# Fluxamasynth32.net
KiCad netlist of a schematic drawn in EAGLE
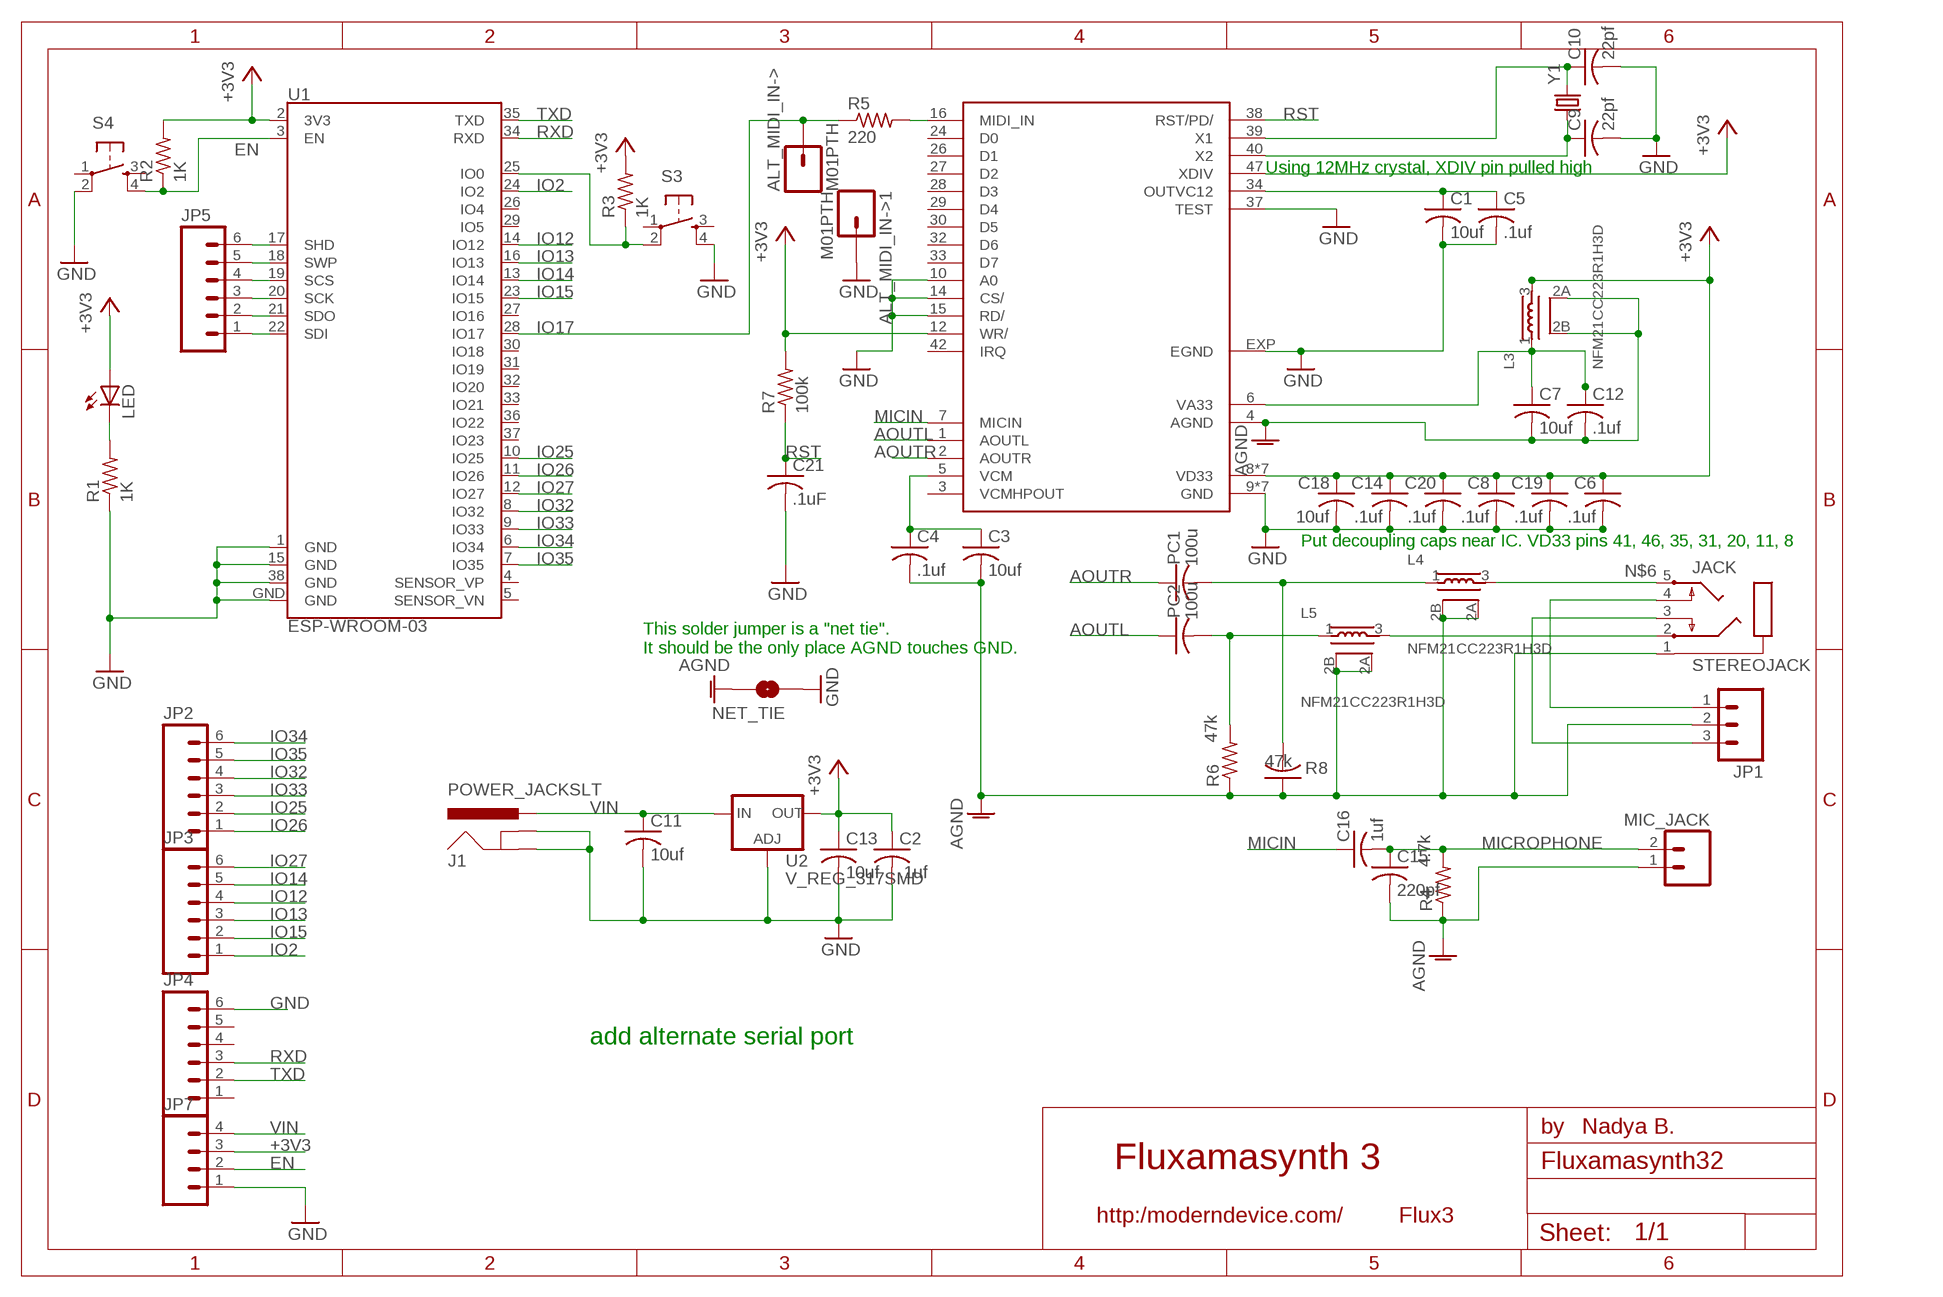
[diagram p0: schematic, sheet 1]

(export (version "E")
  (design (tool "Eeschema 10.0.6"))
  (components
    (comp (ref "ALT_MIDI_IN->")
      (value "M01PTH")
      (footprint "eagle-import:1X01")
      (libsource (lib "eagle-import") (part "M01PTH"))
    )
    (comp (ref "ALT_MIDI_IN->1")
      (value "M01PTH")
      (footprint "eagle-import:1X01")
      (libsource (lib "eagle-import") (part "M01PTH"))
    )
    (comp (ref "C1")
      (value "10uf")
      (footprint "eagle-import:C0805K")
      (libsource (lib "eagle-import") (part "C-USC0805K"))
    )
    (comp (ref "C2")
      (value ".1uf")
      (footprint "eagle-import:C0603K")
      (libsource (lib "eagle-import") (part "C-USC0603K"))
    )
    (comp (ref "C3")
      (value "10uf")
      (footprint "eagle-import:C0805K")
      (libsource (lib "eagle-import") (part "C-USC0805K"))
    )
    (comp (ref "C4")
      (value ".1uf")
      (footprint "eagle-import:C0603K")
      (libsource (lib "eagle-import") (part "C-USC0603K"))
    )
    (comp (ref "C5")
      (value ".1uf")
      (footprint "eagle-import:C0603K")
      (libsource (lib "eagle-import") (part "C-USC0603K"))
    )
    (comp (ref "C6")
      (value ".1uf")
      (footprint "eagle-import:C0603K")
      (libsource (lib "eagle-import") (part "C-USC0603K"))
    )
    (comp (ref "C7")
      (value "10uf")
      (footprint "eagle-import:C0805K")
      (libsource (lib "eagle-import") (part "C-USC0805K"))
    )
    (comp (ref "C8")
      (value ".1uf")
      (footprint "eagle-import:C0603K")
      (libsource (lib "eagle-import") (part "C-USC0603K"))
    )
    (comp (ref "C9")
      (value "22pf")
      (footprint "eagle-import:C0603")
      (libsource (lib "eagle-import") (part "C-USC0603"))
    )
    (comp (ref "C10")
      (value "22pf")
      (footprint "eagle-import:C0603")
      (libsource (lib "eagle-import") (part "C-USC0603"))
    )
    (comp (ref "C11")
      (value "10uf")
      (footprint "eagle-import:C1206")
      (libsource (lib "eagle-import") (part "C-USC1206"))
    )
    (comp (ref "C12")
      (value ".1uf")
      (footprint "eagle-import:C0603K")
      (libsource (lib "eagle-import") (part "C-USC0603K"))
    )
    (comp (ref "C13")
      (value "10uf")
      (footprint "eagle-import:C1206")
      (libsource (lib "eagle-import") (part "C-USC1206"))
    )
    (comp (ref "C14")
      (value ".1uf")
      (footprint "eagle-import:C0603K")
      (libsource (lib "eagle-import") (part "C-USC0603K"))
    )
    (comp (ref "C15")
      (value "220pf")
      (footprint "eagle-import:C0805K")
      (libsource (lib "eagle-import") (part "C-USC0805K"))
    )
    (comp (ref "C16")
      (value "1uf")
      (footprint "eagle-import:C0603K")
      (libsource (lib "eagle-import") (part "C-USC0603K"))
    )
    (comp (ref "C18")
      (value "10uf")
      (footprint "eagle-import:C0603K")
      (libsource (lib "eagle-import") (part "C-USC0603K"))
    )
    (comp (ref "C19")
      (value ".1uf")
      (footprint "eagle-import:C0603K")
      (libsource (lib "eagle-import") (part "C-USC0603K"))
    )
    (comp (ref "C20")
      (value ".1uf")
      (footprint "eagle-import:C0603K")
      (libsource (lib "eagle-import") (part "C-USC0603K"))
    )
    (comp (ref "C21")
      (value ".1uF")
      (footprint "eagle-import:C0603K")
      (libsource (lib "eagle-import") (part "C-USC0603K"))
    )
    (comp (ref "J1")
      (value "POWER_JACKSLT")
      (footprint "eagle-import:POWER_JACK_SLOT")
      (libsource (lib "eagle-import") (part "POWER_JACKSLT"))
    )
    (comp (ref "JACK")
      (value "STEREOJACK")
      (footprint "eagle-import:STX3100")
      (libsource (lib "eagle-import") (part "STEREOJACK"))
    )
    (comp (ref "JP1")
      (value "M03PTH")
      (footprint "eagle-import:1X03")
      (libsource (lib "eagle-import") (part "M03PTH"))
    )
    (comp (ref "JP2")
      (value "M06NO_SILK")
      (footprint "eagle-import:1X06_NO_SILK")
      (libsource (lib "eagle-import") (part "M06NO_SILK"))
    )
    (comp (ref "JP3")
      (value "M06NO_SILK")
      (footprint "eagle-import:1X06_NO_SILK")
      (libsource (lib "eagle-import") (part "M06NO_SILK"))
    )
    (comp (ref "JP4")
      (value "M06NO_SILK")
      (footprint "eagle-import:1X06_NO_SILK")
      (libsource (lib "eagle-import") (part "M06NO_SILK"))
    )
    (comp (ref "JP5")
      (value "M06NO_SILK")
      (footprint "eagle-import:1X06_NO_SILK")
      (libsource (lib "eagle-import") (part "M06NO_SILK"))
    )
    (comp (ref "JP7")
      (value "M041X04_NO_SILK")
      (footprint "eagle-import:1X04_NO_SILK")
      (libsource (lib "eagle-import") (part "M041X04_NO_SILK"))
    )
    (comp (ref "L3")
      (value "NFM21CC223R1H3D")
      (footprint "eagle-import:3PC")
      (libsource (lib "eagle-import") (part "NFM21CC223R1H3D"))
    )
    (comp (ref "L4")
      (value "NFM21CC223R1H3D")
      (footprint "eagle-import:3PC")
      (libsource (lib "eagle-import") (part "NFM21CC223R1H3D"))
    )
    (comp (ref "L5")
      (value "NFM21CC223R1H3D")
      (footprint "eagle-import:3PC")
      (libsource (lib "eagle-import") (part "NFM21CC223R1H3D"))
    )
    (comp (ref "LED")
      (value "LED0603")
      (footprint "eagle-import:LED-0603")
      (libsource (lib "eagle-import") (part "LED0603"))
    )
    (comp (ref "MIC_JACK")
      (value "M02PTH")
      (footprint "eagle-import:1X02")
      (libsource (lib "eagle-import") (part "M02PTH"))
    )
    (comp (ref "NET_TIE")
      (value "MODERNDEVICE_SOLDERJUMPERTRACE")
      (footprint "eagle-import:MODERNDEVICE_SJ_2S-TRACE")
      (libsource (lib "eagle-import") (part "MODERNDEVICE_SOLDERJUMPERTRACE"))
    )
    (comp (ref "PC1")
      (value "100u")
      (footprint "eagle-import:C1206K")
      (libsource (lib "eagle-import") (part "C-USC1206K"))
    )
    (comp (ref "PC2")
      (value "100u")
      (footprint "eagle-import:C1206K")
      (libsource (lib "eagle-import") (part "C-USC1206K"))
    )
    (comp (ref "R1")
      (value "1K")
      (footprint "eagle-import:R0603")
      (libsource (lib "eagle-import") (part "R-US_R0603"))
    )
    (comp (ref "R2")
      (value "1K")
      (footprint "eagle-import:R0603")
      (libsource (lib "eagle-import") (part "R-US_R0603"))
    )
    (comp (ref "R3")
      (value "1K")
      (footprint "eagle-import:R0603")
      (libsource (lib "eagle-import") (part "R-US_R0603"))
    )
    (comp (ref "R4")
      (value "4.7k")
      (footprint "eagle-import:R0603")
      (libsource (lib "eagle-import") (part "R-US_R0603"))
    )
    (comp (ref "R5")
      (value "220")
      (footprint "eagle-import:R0603")
      (libsource (lib "eagle-import") (part "R-US_R0603"))
    )
    (comp (ref "R6")
      (value "47k")
      (footprint "eagle-import:R0603")
      (libsource (lib "eagle-import") (part "R-US_R0603"))
    )
    (comp (ref "R7")
      (value "100k")
      (footprint "eagle-import:R0603")
      (libsource (lib "eagle-import") (part "R-US_R0603"))
    )
    (comp (ref "R8")
      (value "47k")
      (footprint "eagle-import:C0603K")
      (libsource (lib "eagle-import") (part "C-USC0603K"))
    )
    (comp (ref "S3")
      (value "6MM_SWITCH6MM_SWITCH")
      (footprint "eagle-import:6MM_SWITCH")
      (libsource (lib "eagle-import") (part "6MM_SWITCH6MM_SWITCH"))
    )
    (comp (ref "S4")
      (value "6MM_SWITCH6MM_SWITCH")
      (footprint "eagle-import:6MM_SWITCH")
      (libsource (lib "eagle-import") (part "6MM_SWITCH6MM_SWITCH"))
    )
    (comp (ref "SAM2695")
      (value "SAM2695")
      (footprint "eagle-import:QFN48")
      (libsource (lib "eagle-import") (part "SAM2695"))
    )
    (comp (ref "U1")
      (value "ESP-WROOM-03")
      (footprint "eagle-import:ESP-WROOM-03")
      (libsource (lib "eagle-import") (part "ESP-WROOM-03"))
    )
    (comp (ref "U2")
      (value "V_REG_317SMD")
      (footprint "eagle-import:SOT223")
      (libsource (lib "eagle-import") (part "V_REG_317SMD"))
    )
    (comp (ref "Y1")
      (value "CRYSTALTXC-7A")
      (footprint "eagle-import:CRYSTAL-TXC-7A")
      (libsource (lib "eagle-import") (part "CRYSTALTXC-7A"))
    )
  )
  (nets
    (net (code "1") (name "+3V3") (class "Default")
      (node (ref "C13") (pin "1") (pinfunction "1_1") (pintype "passive"))
      (node (ref "C14") (pin "1") (pinfunction "1_1") (pintype "passive"))
      (node (ref "C18") (pin "1") (pinfunction "1_1") (pintype "passive"))
      (node (ref "C19") (pin "1") (pinfunction "1_1") (pintype "passive"))
      (node (ref "C2") (pin "1") (pinfunction "1_1") (pintype "passive"))
      (node (ref "C20") (pin "1") (pinfunction "1_1") (pintype "passive"))
      (node (ref "C6") (pin "1") (pinfunction "1_1") (pintype "passive"))
      (node (ref "C8") (pin "1") (pinfunction "1_1") (pintype "passive"))
      (node (ref "JP7") (pin "3") (pinfunction "3_3") (pintype "passive"))
      (node (ref "L3") (pin "3") (pinfunction "3_3") (pintype "bidirectional"))
      (node (ref "LED") (pin "A") (pinfunction "A_A") (pintype "passive"))
      (node (ref "R2") (pin "2") (pinfunction "2_2") (pintype "passive"))
      (node (ref "R3") (pin "2") (pinfunction "2_2") (pintype "passive"))
      (node (ref "R7") (pin "2") (pinfunction "2_2") (pintype "passive"))
      (node (ref "SAM2695") (pin "11") (pinfunction "VD33_11") (pintype "power_in"))
      (node (ref "SAM2695") (pin "12") (pinfunction "WR/_12") (pintype "input"))
      (node (ref "SAM2695") (pin "20") (pinfunction "VD33_20") (pintype "power_in"))
      (node (ref "SAM2695") (pin "31") (pinfunction "VD33_31") (pintype "power_in"))
      (node (ref "SAM2695") (pin "35") (pinfunction "VD33_35") (pintype "power_in"))
      (node (ref "SAM2695") (pin "41") (pinfunction "VD33_41") (pintype "power_in"))
      (node (ref "SAM2695") (pin "46") (pinfunction "VD33_46") (pintype "power_in"))
      (node (ref "SAM2695") (pin "47") (pinfunction "XDIV_47") (pintype "input"))
      (node (ref "SAM2695") (pin "8") (pinfunction "VD33_8") (pintype "power_in"))
      (node (ref "U1") (pin "2") (pinfunction "3V3_2") (pintype "bidirectional"))
      (node (ref "U2") (pin "2") (pinfunction "OUT_2") (pintype "output"))
      (node (ref "U2") (pin "4") (pinfunction "OUT_4") (pintype "output"))
    )
    (net (code "2") (name "/AOUTL") (class "Default")
      (node (ref "PC2") (pin "1") (pinfunction "1_1") (pintype "passive"))
      (node (ref "SAM2695") (pin "1") (pinfunction "AOUTL_1") (pintype "output"))
    )
    (net (code "3") (name "/AOUTR") (class "Default")
      (node (ref "PC1") (pin "1") (pinfunction "1_1") (pintype "passive"))
      (node (ref "SAM2695") (pin "2") (pinfunction "AOUTR_2") (pintype "output"))
    )
    (net (code "4") (name "/EN") (class "Default")
      (node (ref "JP7") (pin "2") (pinfunction "2_2") (pintype "passive"))
      (node (ref "R2") (pin "1") (pinfunction "1_1") (pintype "passive"))
      (node (ref "S4") (pin "4") (pinfunction "S1_4") (pintype "passive"))
      (node (ref "U1") (pin "3") (pinfunction "EN_3") (pintype "bidirectional"))
    )
    (net (code "5") (name "/IO2") (class "Default")
      (node (ref "JP3") (pin "1") (pinfunction "1_1") (pintype "passive"))
      (node (ref "U1") (pin "24") (pinfunction "IO2_24") (pintype "bidirectional"))
    )
    (net (code "6") (name "/IO12") (class "Default")
      (node (ref "JP3") (pin "4") (pinfunction "4_4") (pintype "passive"))
      (node (ref "U1") (pin "14") (pinfunction "IO12_14") (pintype "bidirectional"))
    )
    (net (code "7") (name "/IO13") (class "Default")
      (node (ref "JP3") (pin "3") (pinfunction "3_3") (pintype "passive"))
      (node (ref "U1") (pin "16") (pinfunction "IO13_16") (pintype "bidirectional"))
    )
    (net (code "8") (name "/IO14") (class "Default")
      (node (ref "JP3") (pin "5") (pinfunction "5_5") (pintype "passive"))
      (node (ref "U1") (pin "13") (pinfunction "IO14_13") (pintype "bidirectional"))
    )
    (net (code "9") (name "/IO15") (class "Default")
      (node (ref "JP3") (pin "2") (pinfunction "2_2") (pintype "passive"))
      (node (ref "U1") (pin "23") (pinfunction "IO15_23") (pintype "bidirectional"))
    )
    (net (code "10") (name "/IO17") (class "Default")
      (node (ref "ALT_MIDI_IN->") (pin "1") (pinfunction "1_1") (pintype "passive"))
      (node (ref "R5") (pin "1") (pinfunction "1_1") (pintype "passive"))
      (node (ref "U1") (pin "28") (pinfunction "IO17_28") (pintype "bidirectional"))
    )
    (net (code "11") (name "/IO25") (class "Default")
      (node (ref "JP2") (pin "2") (pinfunction "2_2") (pintype "passive"))
      (node (ref "U1") (pin "10") (pinfunction "IO25_10") (pintype "bidirectional"))
    )
    (net (code "12") (name "/IO26") (class "Default")
      (node (ref "JP2") (pin "1") (pinfunction "1_1") (pintype "passive"))
      (node (ref "U1") (pin "11") (pinfunction "IO26_11") (pintype "bidirectional"))
    )
    (net (code "13") (name "/IO27") (class "Default")
      (node (ref "JP3") (pin "6") (pinfunction "6_6") (pintype "passive"))
      (node (ref "U1") (pin "12") (pinfunction "IO27_12") (pintype "bidirectional"))
    )
    (net (code "14") (name "/IO32") (class "Default")
      (node (ref "JP2") (pin "4") (pinfunction "4_4") (pintype "passive"))
      (node (ref "U1") (pin "8") (pinfunction "IO32_8") (pintype "bidirectional"))
    )
    (net (code "15") (name "/IO33") (class "Default")
      (node (ref "JP2") (pin "3") (pinfunction "3_3") (pintype "passive"))
      (node (ref "U1") (pin "9") (pinfunction "IO33_9") (pintype "bidirectional"))
    )
    (net (code "16") (name "/IO34") (class "Default")
      (node (ref "JP2") (pin "6") (pinfunction "6_6") (pintype "passive"))
      (node (ref "U1") (pin "6") (pinfunction "IO34_6") (pintype "bidirectional"))
    )
    (net (code "17") (name "/IO35") (class "Default")
      (node (ref "JP2") (pin "5") (pinfunction "5_5") (pintype "passive"))
      (node (ref "U1") (pin "7") (pinfunction "IO35_7") (pintype "bidirectional"))
    )
    (net (code "18") (name "/MICIN") (class "Default")
      (node (ref "C16") (pin "1") (pinfunction "1_1") (pintype "passive"))
      (node (ref "SAM2695") (pin "7") (pinfunction "MICIN_7") (pintype "input"))
    )
    (net (code "19") (name "/MICROPHONE") (class "Default")
      (node (ref "C15") (pin "1") (pinfunction "1_1") (pintype "passive"))
      (node (ref "C16") (pin "2") (pinfunction "2_2") (pintype "passive"))
      (node (ref "MIC_JACK") (pin "2") (pinfunction "2_2") (pintype "passive"))
      (node (ref "R4") (pin "2") (pinfunction "2_2") (pintype "passive"))
    )
    (net (code "20") (name "/N$6") (class "Default")
      (node (ref "JACK") (pin "5") (pinfunction "5_5") (pintype "passive"))
      (node (ref "L4") (pin "3") (pinfunction "3_3") (pintype "bidirectional"))
    )
    (net (code "21") (name "/RST") (class "Default")
      (node (ref "C21") (pin "1") (pinfunction "1_1") (pintype "passive"))
      (node (ref "R7") (pin "1") (pinfunction "1_1") (pintype "passive"))
      (node (ref "SAM2695") (pin "38") (pinfunction "RST/PD/_38") (pintype "input"))
    )
    (net (code "22") (name "/RXD") (class "Default")
      (node (ref "JP4") (pin "3") (pinfunction "3_3") (pintype "passive"))
      (node (ref "U1") (pin "34") (pinfunction "RXD_34") (pintype "bidirectional"))
    )
    (net (code "23") (name "/TXD") (class "Default")
      (node (ref "JP4") (pin "2") (pinfunction "2_2") (pintype "passive"))
      (node (ref "U1") (pin "35") (pinfunction "TXD_35") (pintype "bidirectional"))
    )
    (net (code "24") (name "/VIN") (class "Default")
      (node (ref "C11") (pin "1") (pinfunction "1_1") (pintype "passive"))
      (node (ref "J1") (pin "PWR") (pinfunction "PWR_PWR") (pintype "bidirectional"))
      (node (ref "JP7") (pin "4") (pinfunction "4_4") (pintype "passive"))
      (node (ref "U2") (pin "3") (pinfunction "IN_3") (pintype "input"))
    )
    (net (code "25") (name "AGND") (class "Default")
      (node (ref "C12") (pin "2") (pinfunction "2_2") (pintype "passive"))
      (node (ref "C15") (pin "2") (pinfunction "2_2") (pintype "passive"))
      (node (ref "C3") (pin "2") (pinfunction "2_2") (pintype "passive"))
      (node (ref "C4") (pin "2") (pinfunction "2_2") (pintype "passive"))
      (node (ref "C7") (pin "2") (pinfunction "2_2") (pintype "passive"))
      (node (ref "JACK") (pin "1") (pinfunction "1_1") (pintype "passive"))
      (node (ref "JP1") (pin "2") (pinfunction "2_2") (pintype "passive"))
      (node (ref "L3") (pin "2A") (pinfunction "2A_2A") (pintype "power_in"))
      (node (ref "L3") (pin "2B") (pinfunction "2B_2B") (pintype "power_in"))
      (node (ref "L4") (pin "2A") (pinfunction "2A_2A") (pintype "power_in"))
      (node (ref "L4") (pin "2B") (pinfunction "2B_2B") (pintype "power_in"))
      (node (ref "L5") (pin "2A") (pinfunction "2A_2A") (pintype "power_in"))
      (node (ref "L5") (pin "2B") (pinfunction "2B_2B") (pintype "power_in"))
      (node (ref "MIC_JACK") (pin "1") (pinfunction "1_1") (pintype "passive"))
      (node (ref "NET_TIE") (pin "2") (pinfunction "2_2") (pintype "passive"))
      (node (ref "R4") (pin "1") (pinfunction "1_1") (pintype "passive"))
      (node (ref "R6") (pin "1") (pinfunction "1_1") (pintype "passive"))
      (node (ref "R8") (pin "1") (pinfunction "1_1") (pintype "passive"))
      (node (ref "SAM2695") (pin "4") (pinfunction "AGND_4") (pintype "power_in"))
    )
    (net (code "26") (name "GND") (class "Default")
      (node (ref "ALT_MIDI_IN->1") (pin "1") (pinfunction "1_1") (pintype "passive"))
      (node (ref "C1") (pin "2") (pinfunction "2_2") (pintype "passive"))
      (node (ref "C10") (pin "2") (pinfunction "2_2") (pintype "passive"))
      (node (ref "C11") (pin "2") (pinfunction "2_2") (pintype "passive"))
      (node (ref "C13") (pin "2") (pinfunction "2_2") (pintype "passive"))
      (node (ref "C14") (pin "2") (pinfunction "2_2") (pintype "passive"))
      (node (ref "C18") (pin "2") (pinfunction "2_2") (pintype "passive"))
      (node (ref "C19") (pin "2") (pinfunction "2_2") (pintype "passive"))
      (node (ref "C2") (pin "2") (pinfunction "2_2") (pintype "passive"))
      (node (ref "C20") (pin "2") (pinfunction "2_2") (pintype "passive"))
      (node (ref "C21") (pin "2") (pinfunction "2_2") (pintype "passive"))
      (node (ref "C5") (pin "2") (pinfunction "2_2") (pintype "passive"))
      (node (ref "C6") (pin "2") (pinfunction "2_2") (pintype "passive"))
      (node (ref "C8") (pin "2") (pinfunction "2_2") (pintype "passive"))
      (node (ref "C9") (pin "2") (pinfunction "2_2") (pintype "passive"))
      (node (ref "J1") (pin "GND@1") (pinfunction "GNDBREAK_GND@1") (pintype "bidirectional"))
      (node (ref "J1") (pin "GND@2") (pinfunction "GND_GND@2") (pintype "bidirectional"))
      (node (ref "JP4") (pin "6") (pinfunction "6_6") (pintype "passive"))
      (node (ref "JP7") (pin "1") (pinfunction "1_1") (pintype "passive"))
      (node (ref "NET_TIE") (pin "1") (pinfunction "1_1") (pintype "passive"))
      (node (ref "R1") (pin "1") (pinfunction "1_1") (pintype "passive"))
      (node (ref "S3") (pin "4") (pinfunction "S1_4") (pintype "passive"))
      (node (ref "S4") (pin "2") (pinfunction "P1_2") (pintype "passive"))
      (node (ref "SAM2695") (pin "10") (pinfunction "A0_10") (pintype "input"))
      (node (ref "SAM2695") (pin "13") (pinfunction "GND_13") (pintype "power_in"))
      (node (ref "SAM2695") (pin "14") (pinfunction "CS/_14") (pintype "input"))
      (node (ref "SAM2695") (pin "15") (pinfunction "RD/_15") (pintype "input"))
      (node (ref "SAM2695") (pin "18") (pinfunction "GND_18") (pintype "power_in"))
      (node (ref "SAM2695") (pin "25") (pinfunction "GND_25") (pintype "power_in"))
      (node (ref "SAM2695") (pin "36") (pinfunction "GND_36") (pintype "power_in"))
      (node (ref "SAM2695") (pin "37") (pinfunction "TEST_37") (pintype "input"))
      (node (ref "SAM2695") (pin "45") (pinfunction "GND_45") (pintype "power_in"))
      (node (ref "SAM2695") (pin "48") (pinfunction "GND_48") (pintype "power_in"))
      (node (ref "SAM2695") (pin "9") (pinfunction "GND_9") (pintype "power_in"))
      (node (ref "SAM2695") (pin "EXP") (pinfunction "EGND_EXP") (pintype "power_in"))
      (node (ref "U1") (pin "1") (pinfunction "GND_1") (pintype "bidirectional"))
      (node (ref "U1") (pin "15") (pinfunction "GND_15") (pintype "bidirectional"))
      (node (ref "U1") (pin "38") (pinfunction "GND_38") (pintype "bidirectional"))
      (node (ref "U1") (pin "GND") (pinfunction "GND_GND") (pintype "bidirectional"))
      (node (ref "U2") (pin "1") (pinfunction "ADJ_1") (pintype "input"))
    )
    (net (code "27") (name "Net-(JACK-Pad2)") (class "Default")
      (node (ref "JACK") (pin "2") (pinfunction "2_2") (pintype "passive"))
      (node (ref "L5") (pin "3") (pinfunction "3_3") (pintype "bidirectional"))
    )
    (net (code "28") (name "Net-(JACK-Pad3)") (class "Default")
      (node (ref "JACK") (pin "3") (pinfunction "3_3") (pintype "passive"))
      (node (ref "JP1") (pin "3") (pinfunction "3_3") (pintype "passive"))
    )
    (net (code "29") (name "Net-(JACK-Pad4)") (class "Default")
      (node (ref "JACK") (pin "4") (pinfunction "4_4") (pintype "passive"))
      (node (ref "JP1") (pin "1") (pinfunction "1_1") (pintype "passive"))
    )
    (net (code "30") (name "Net-(L4-Pad1)") (class "Default")
      (node (ref "L4") (pin "1") (pinfunction "1_1") (pintype "bidirectional"))
      (node (ref "PC1") (pin "2") (pinfunction "2_2") (pintype "passive"))
      (node (ref "R8") (pin "2") (pinfunction "2_2") (pintype "passive"))
    )
    (net (code "31") (name "Net-(L5-Pad1)") (class "Default")
      (node (ref "L5") (pin "1") (pinfunction "1_1") (pintype "bidirectional"))
      (node (ref "PC2") (pin "2") (pinfunction "2_2") (pintype "passive"))
      (node (ref "R6") (pin "2") (pinfunction "2_2") (pintype "passive"))
    )
    (net (code "32") (name "Net-(LED-PadC)") (class "Default")
      (node (ref "LED") (pin "C") (pinfunction "C_C") (pintype "passive"))
      (node (ref "R1") (pin "2") (pinfunction "2_2") (pintype "passive"))
    )
    (net (code "33") (name "Net-(S3-P1)") (class "Default")
      (node (ref "R3") (pin "1") (pinfunction "1_1") (pintype "passive"))
      (node (ref "S3") (pin "2") (pinfunction "P1_2") (pintype "passive"))
      (node (ref "U1") (pin "25") (pinfunction "IO0_25") (pintype "bidirectional"))
    )
    (net (code "34") (name "Net-(SAM2695-MIDI_IN)") (class "Default")
      (node (ref "R5") (pin "2") (pinfunction "2_2") (pintype "passive"))
      (node (ref "SAM2695") (pin "16") (pinfunction "MIDI_IN_16") (pintype "input"))
    )
    (net (code "35") (name "Net-(SAM2695-OUTVC12)") (class "Default")
      (node (ref "C1") (pin "1") (pinfunction "1_1") (pintype "passive"))
      (node (ref "C5") (pin "1") (pinfunction "1_1") (pintype "passive"))
      (node (ref "SAM2695") (pin "34") (pinfunction "OUTVC12_34") (pintype "power_in"))
    )
    (net (code "36") (name "Net-(SAM2695-VA33)") (class "Default")
      (node (ref "C12") (pin "1") (pinfunction "1_1") (pintype "passive"))
      (node (ref "C7") (pin "1") (pinfunction "1_1") (pintype "passive"))
      (node (ref "L3") (pin "1") (pinfunction "1_1") (pintype "bidirectional"))
      (node (ref "SAM2695") (pin "6") (pinfunction "VA33_6") (pintype "power_in"))
    )
    (net (code "37") (name "Net-(SAM2695-VCM)") (class "Default")
      (node (ref "C3") (pin "1") (pinfunction "1_1") (pintype "passive"))
      (node (ref "C4") (pin "1") (pinfunction "1_1") (pintype "passive"))
      (node (ref "SAM2695") (pin "5") (pinfunction "VCM_5") (pintype "output"))
    )
    (net (code "38") (name "Net-(SAM2695-X1)") (class "Default")
      (node (ref "C10") (pin "1") (pinfunction "1_1") (pintype "passive"))
      (node (ref "SAM2695") (pin "39") (pinfunction "X1_39") (pintype "bidirectional"))
      (node (ref "Y1") (pin "P$2") (pinfunction "2_P$2") (pintype "passive"))
    )
    (net (code "39") (name "Net-(SAM2695-X2)") (class "Default")
      (node (ref "C9") (pin "1") (pinfunction "1_1") (pintype "passive"))
      (node (ref "SAM2695") (pin "40") (pinfunction "X2_40") (pintype "bidirectional"))
      (node (ref "Y1") (pin "P$1") (pinfunction "1_P$1") (pintype "passive"))
    )
    (net (code "40") (name "Net-(U1-SCK)") (class "Default")
      (node (ref "JP5") (pin "3") (pinfunction "3_3") (pintype "passive"))
      (node (ref "U1") (pin "20") (pinfunction "SCK_20") (pintype "bidirectional"))
    )
    (net (code "41") (name "Net-(U1-SCS)") (class "Default")
      (node (ref "JP5") (pin "4") (pinfunction "4_4") (pintype "passive"))
      (node (ref "U1") (pin "19") (pinfunction "SCS_19") (pintype "bidirectional"))
    )
    (net (code "42") (name "Net-(U1-SDI)") (class "Default")
      (node (ref "JP5") (pin "1") (pinfunction "1_1") (pintype "passive"))
      (node (ref "U1") (pin "22") (pinfunction "SDI_22") (pintype "bidirectional"))
    )
    (net (code "43") (name "Net-(U1-SDO)") (class "Default")
      (node (ref "JP5") (pin "2") (pinfunction "2_2") (pintype "passive"))
      (node (ref "U1") (pin "21") (pinfunction "SDO_21") (pintype "bidirectional"))
    )
    (net (code "44") (name "Net-(U1-SHD)") (class "Default")
      (node (ref "JP5") (pin "6") (pinfunction "6_6") (pintype "passive"))
      (node (ref "U1") (pin "17") (pinfunction "SHD_17") (pintype "bidirectional"))
    )
    (net (code "45") (name "Net-(U1-SWP)") (class "Default")
      (node (ref "JP5") (pin "5") (pinfunction "5_5") (pintype "passive"))
      (node (ref "U1") (pin "18") (pinfunction "SWP_18") (pintype "bidirectional"))
    )
    (net (code "46") (name "unconnected-(JP4-Pad1)") (class "Default")
      (node (ref "JP4") (pin "1") (pinfunction "1_1") (pintype "passive"))
    )
    (net (code "47") (name "unconnected-(JP4-Pad4)") (class "Default")
      (node (ref "JP4") (pin "4") (pinfunction "4_4") (pintype "passive"))
    )
    (net (code "48") (name "unconnected-(JP4-Pad5)") (class "Default")
      (node (ref "JP4") (pin "5") (pinfunction "5_5") (pintype "passive"))
    )
    (net (code "49") (name "unconnected-(S3-P-Pad1)") (class "Default")
      (node (ref "S3") (pin "1") (pinfunction "P_1") (pintype "passive"))
    )
    (net (code "50") (name "unconnected-(S3-S-Pad3)") (class "Default")
      (node (ref "S3") (pin "3") (pinfunction "S_3") (pintype "passive"))
    )
    (net (code "51") (name "unconnected-(S4-P-Pad1)") (class "Default")
      (node (ref "S4") (pin "1") (pinfunction "P_1") (pintype "passive"))
    )
    (net (code "52") (name "unconnected-(S4-S-Pad3)") (class "Default")
      (node (ref "S4") (pin "3") (pinfunction "S_3") (pintype "passive"))
    )
    (net (code "53") (name "unconnected-(SAM2695-D0-Pad24)") (class "Default")
      (node (ref "SAM2695") (pin "24") (pinfunction "D0_24") (pintype "bidirectional"))
    )
    (net (code "54") (name "unconnected-(SAM2695-D1-Pad26)") (class "Default")
      (node (ref "SAM2695") (pin "26") (pinfunction "D1_26") (pintype "bidirectional"))
    )
    (net (code "55") (name "unconnected-(SAM2695-D2-Pad27)") (class "Default")
      (node (ref "SAM2695") (pin "27") (pinfunction "D2_27") (pintype "bidirectional"))
    )
    (net (code "56") (name "unconnected-(SAM2695-D3-Pad28)") (class "Default")
      (node (ref "SAM2695") (pin "28") (pinfunction "D3_28") (pintype "bidirectional"))
    )
    (net (code "57") (name "unconnected-(SAM2695-D4-Pad29)") (class "Default")
      (node (ref "SAM2695") (pin "29") (pinfunction "D4_29") (pintype "bidirectional"))
    )
    (net (code "58") (name "unconnected-(SAM2695-D5-Pad30)") (class "Default")
      (node (ref "SAM2695") (pin "30") (pinfunction "D5_30") (pintype "bidirectional"))
    )
    (net (code "59") (name "unconnected-(SAM2695-D6-Pad32)") (class "Default")
      (node (ref "SAM2695") (pin "32") (pinfunction "D6_32") (pintype "bidirectional"))
    )
    (net (code "60") (name "unconnected-(SAM2695-D7-Pad33)") (class "Default")
      (node (ref "SAM2695") (pin "33") (pinfunction "D7_33") (pintype "bidirectional"))
    )
    (net (code "61") (name "unconnected-(SAM2695-IRQ-Pad42)") (class "Default")
      (node (ref "SAM2695") (pin "42") (pinfunction "IRQ_42") (pintype "output"))
    )
    (net (code "62") (name "unconnected-(SAM2695-VCMHPOUT-Pad3)") (class "Default")
      (node (ref "SAM2695") (pin "3") (pinfunction "VCMHPOUT_3") (pintype "output"))
    )
    (net (code "63") (name "unconnected-(U1-IO4-Pad26)") (class "Default")
      (node (ref "U1") (pin "26") (pinfunction "IO4_26") (pintype "bidirectional"))
    )
    (net (code "64") (name "unconnected-(U1-IO5-Pad29)") (class "Default")
      (node (ref "U1") (pin "29") (pinfunction "IO5_29") (pintype "bidirectional"))
    )
    (net (code "65") (name "unconnected-(U1-IO16-Pad27)") (class "Default")
      (node (ref "U1") (pin "27") (pinfunction "IO16_27") (pintype "bidirectional"))
    )
    (net (code "66") (name "unconnected-(U1-IO18-Pad30)") (class "Default")
      (node (ref "U1") (pin "30") (pinfunction "IO18_30") (pintype "bidirectional"))
    )
    (net (code "67") (name "unconnected-(U1-IO19-Pad31)") (class "Default")
      (node (ref "U1") (pin "31") (pinfunction "IO19_31") (pintype "bidirectional"))
    )
    (net (code "68") (name "unconnected-(U1-IO20-Pad32)") (class "Default")
      (node (ref "U1") (pin "32") (pinfunction "IO20_32") (pintype "bidirectional"))
    )
    (net (code "69") (name "unconnected-(U1-IO21-Pad33)") (class "Default")
      (node (ref "U1") (pin "33") (pinfunction "IO21_33") (pintype "bidirectional"))
    )
    (net (code "70") (name "unconnected-(U1-IO22-Pad36)") (class "Default")
      (node (ref "U1") (pin "36") (pinfunction "IO22_36") (pintype "bidirectional"))
    )
    (net (code "71") (name "unconnected-(U1-IO23-Pad37)") (class "Default")
      (node (ref "U1") (pin "37") (pinfunction "IO23_37") (pintype "bidirectional"))
    )
    (net (code "72") (name "unconnected-(U1-SENSOR_VN-Pad5)") (class "Default")
      (node (ref "U1") (pin "5") (pinfunction "SENSOR_VN_5") (pintype "bidirectional"))
    )
    (net (code "73") (name "unconnected-(U1-SENSOR_VP-Pad4)") (class "Default")
      (node (ref "U1") (pin "4") (pinfunction "SENSOR_VP_4") (pintype "bidirectional"))
    )
  )
)
